# Controller.net
KiCad netlist of a schematic drawn in EAGLE
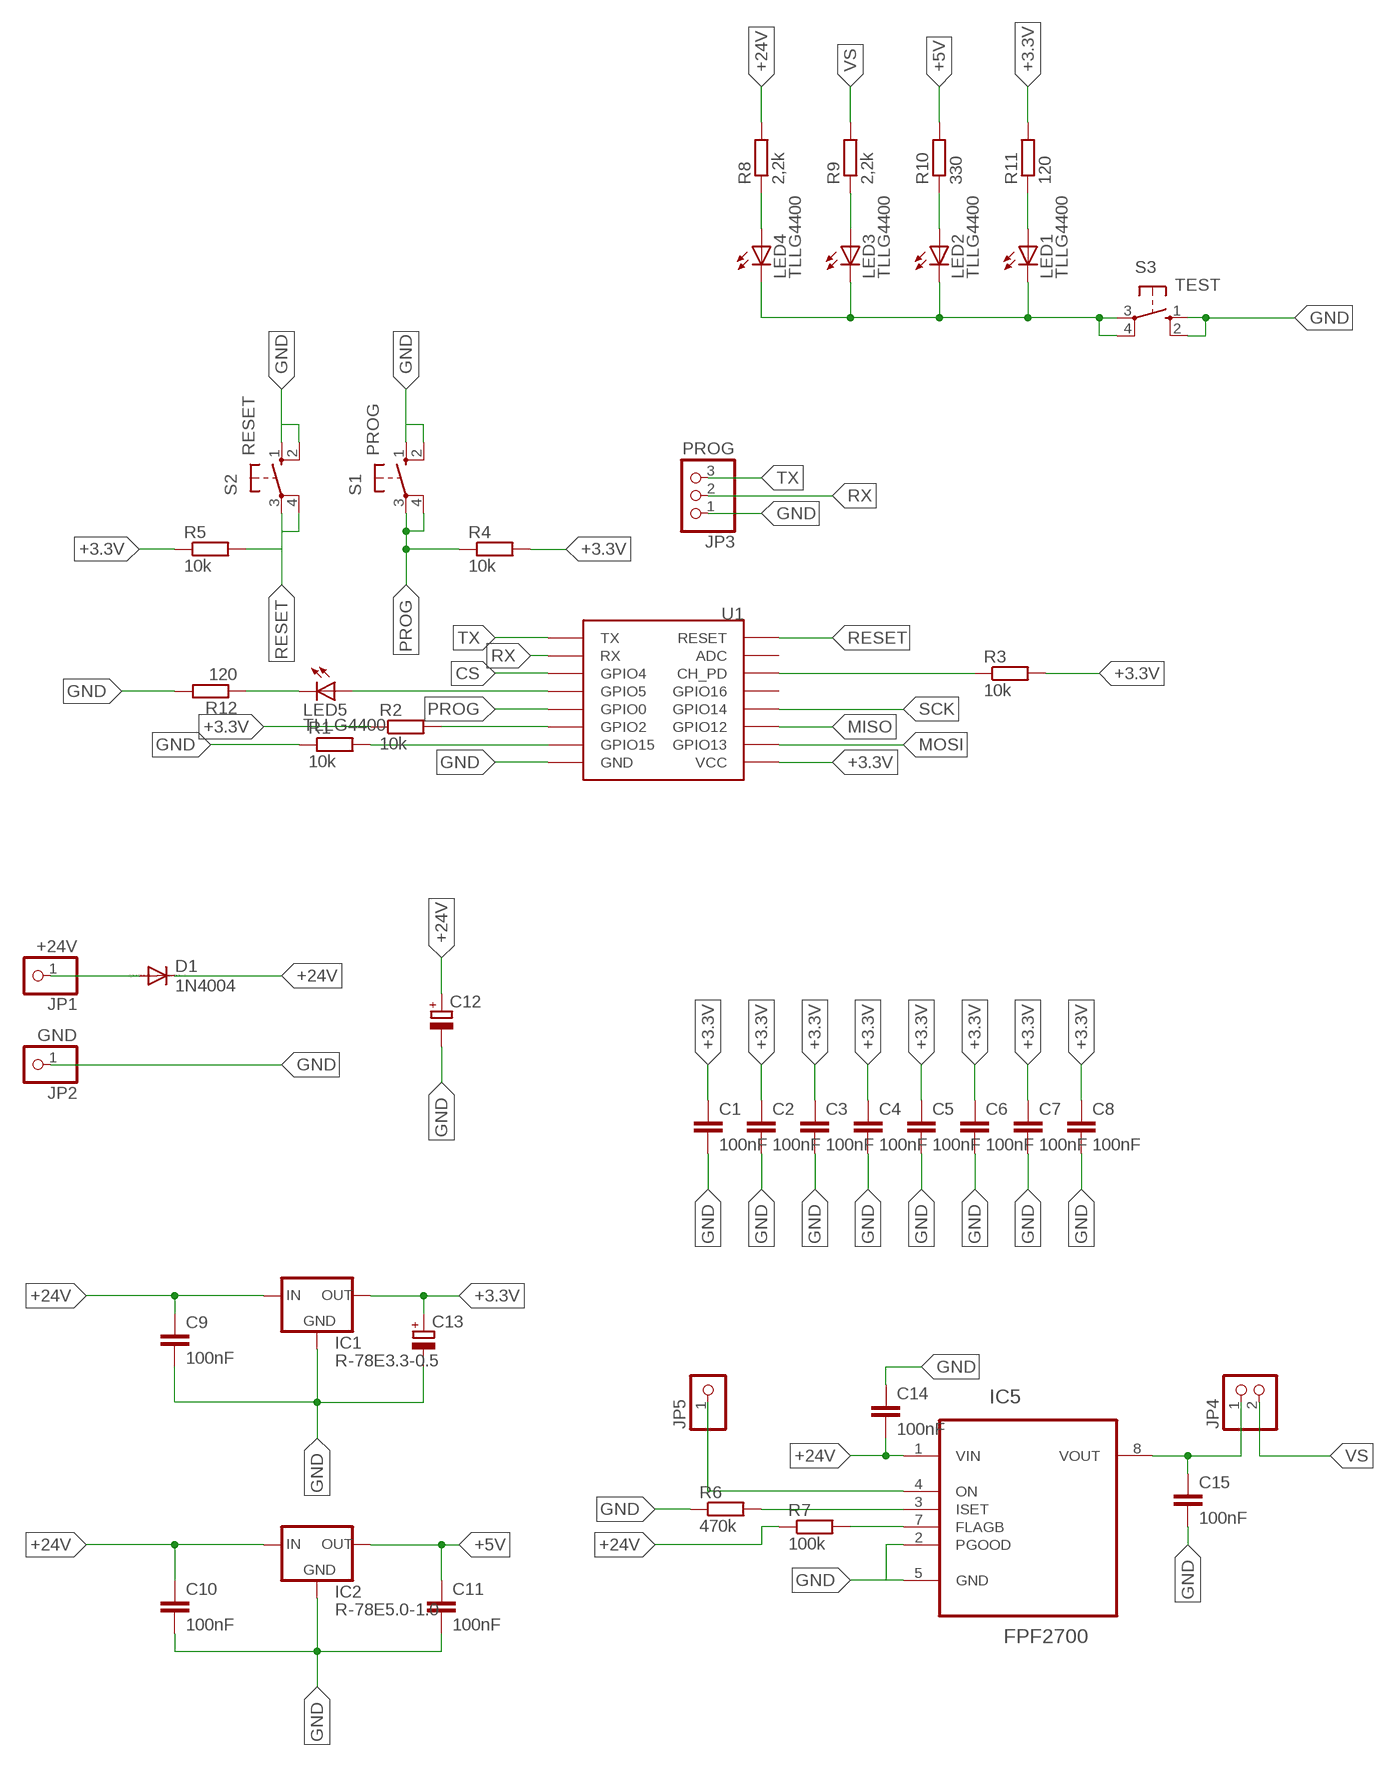
[diagram p0: schematic, sheet 1, part 1 of 2]
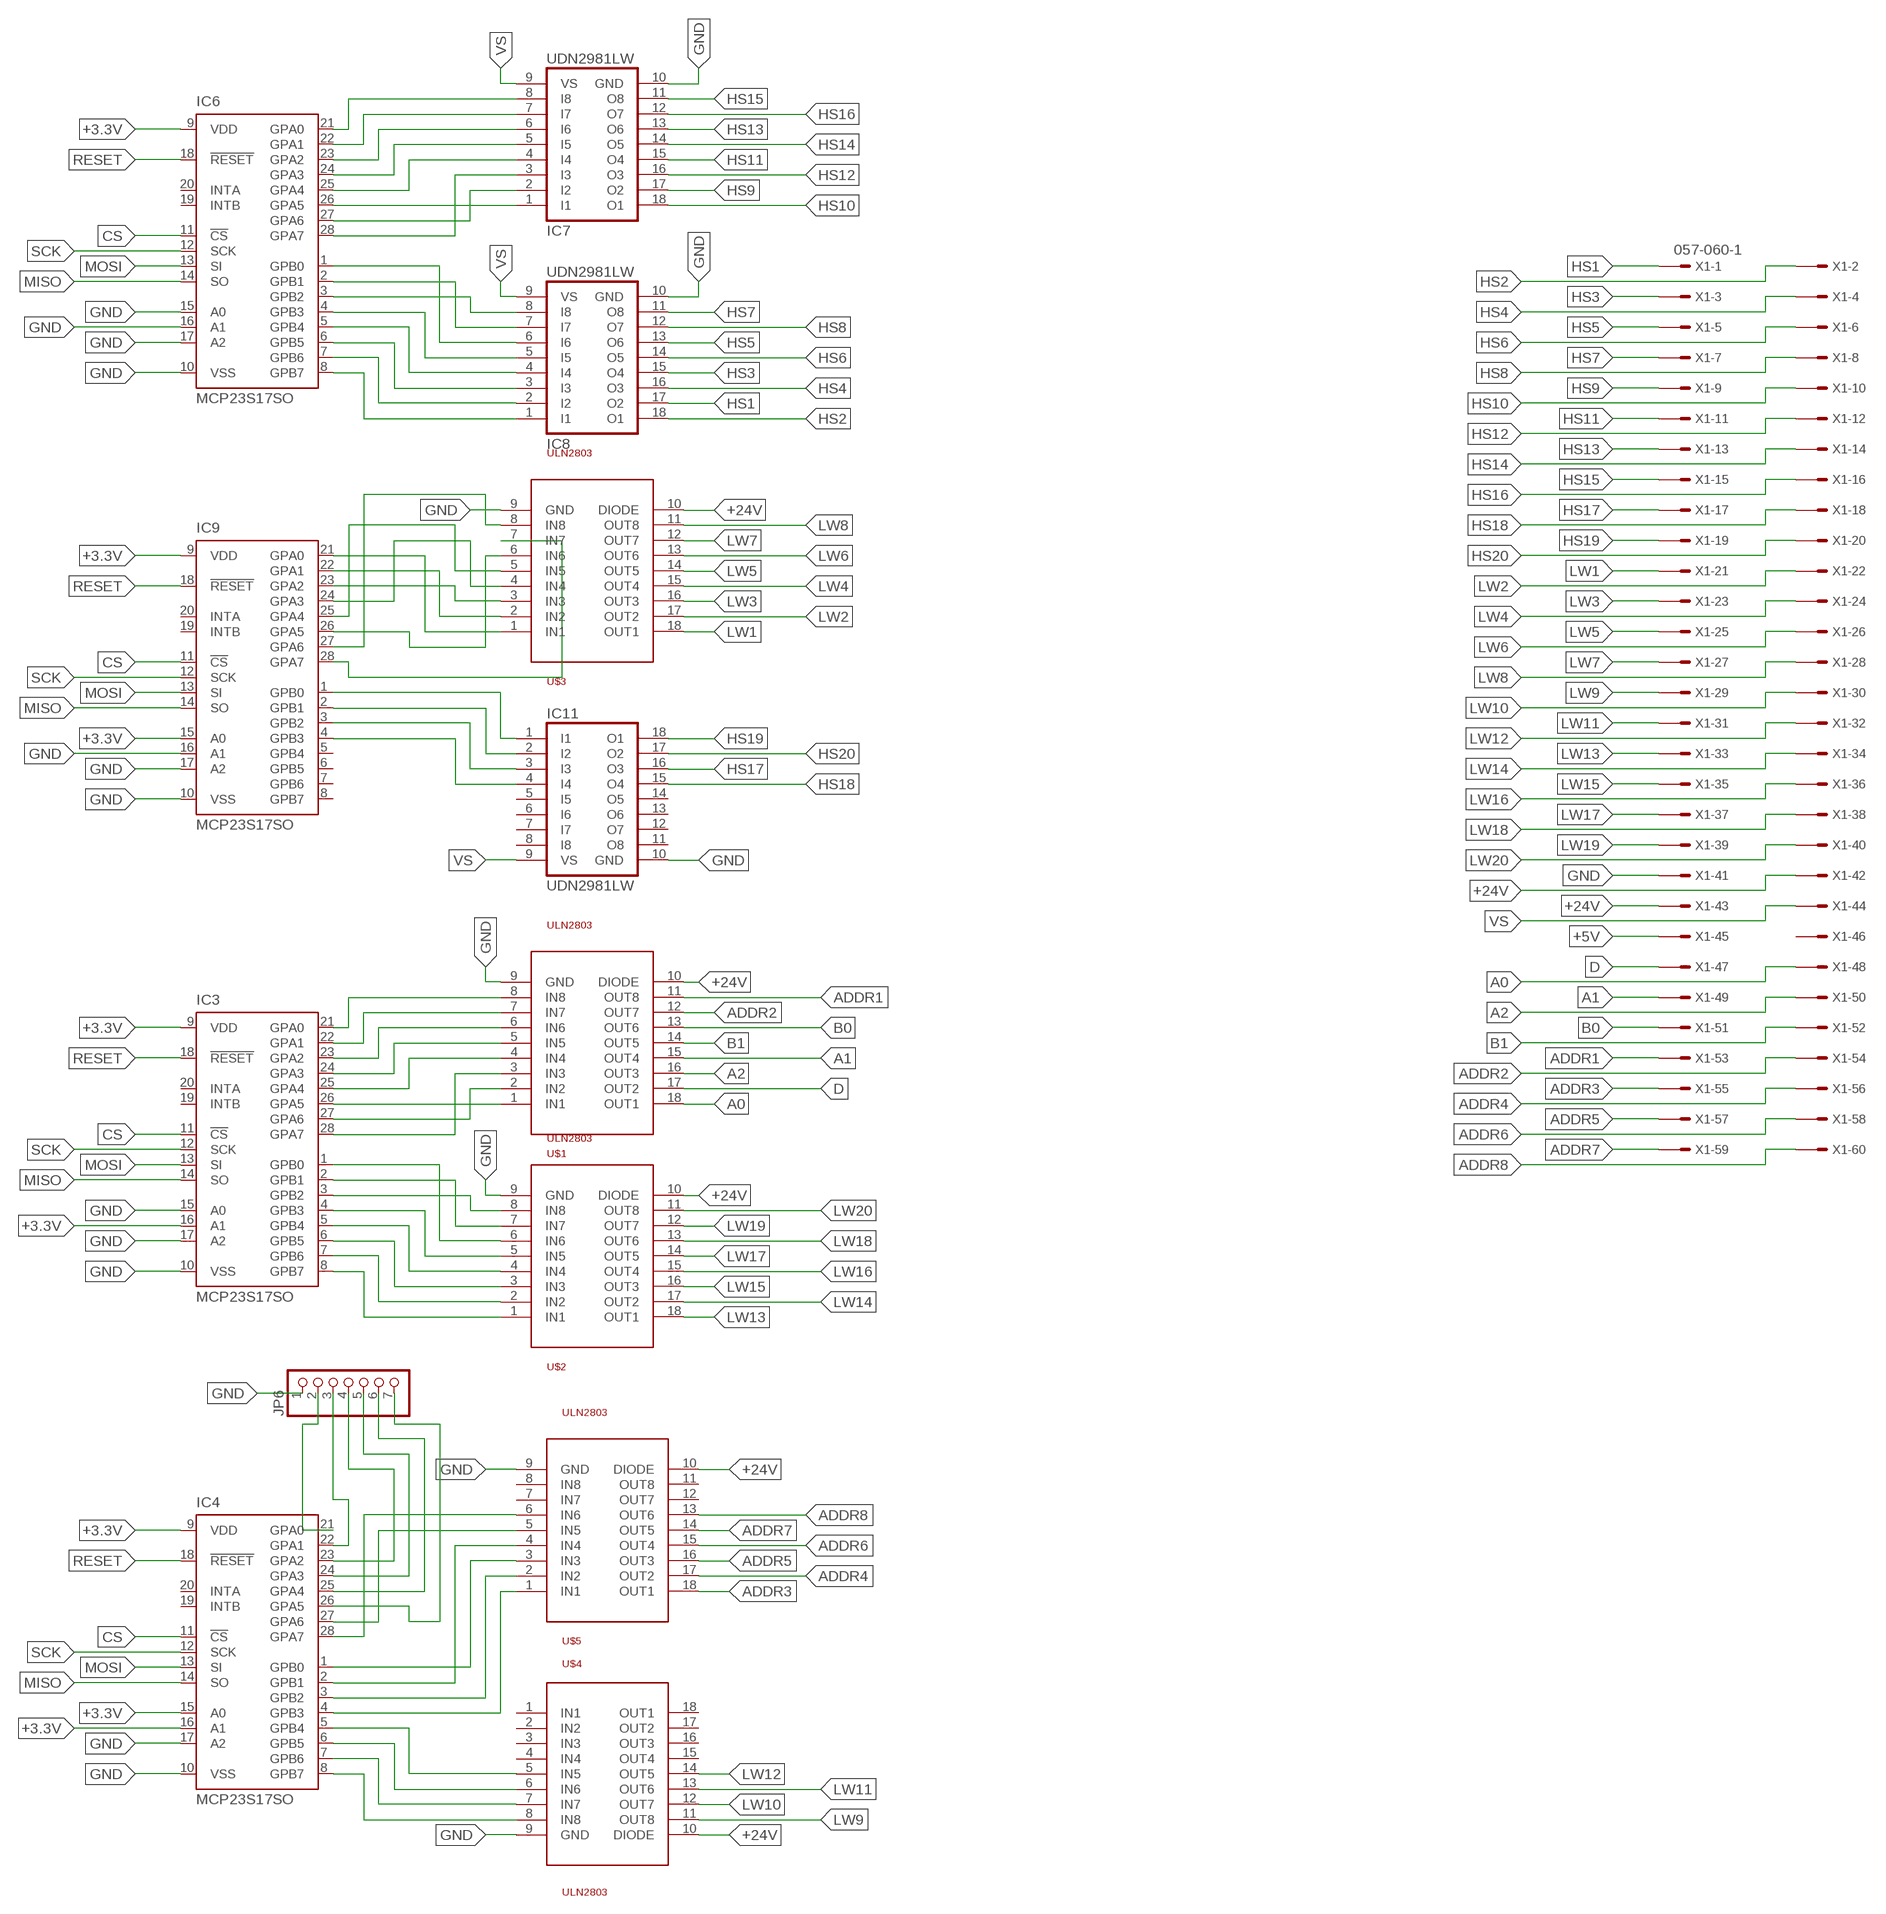
[diagram p1: schematic, sheet 1, part 2 of 2]

(export (version "E")
  (design (tool "Eeschema 10.0.6"))
  (components
    (comp (ref "C1")
      (value "100nF")
      (footprint "eagle-import:C1206")
      (libsource (lib "eagle-import") (part "C-EUC1206"))
    )
    (comp (ref "C2")
      (value "100nF")
      (footprint "eagle-import:C1206")
      (libsource (lib "eagle-import") (part "C-EUC1206"))
    )
    (comp (ref "C3")
      (value "100nF")
      (footprint "eagle-import:C1206")
      (libsource (lib "eagle-import") (part "C-EUC1206"))
    )
    (comp (ref "C4")
      (value "100nF")
      (footprint "eagle-import:C1206")
      (libsource (lib "eagle-import") (part "C-EUC1206"))
    )
    (comp (ref "C5")
      (value "100nF")
      (footprint "eagle-import:C1206")
      (libsource (lib "eagle-import") (part "C-EUC1206"))
    )
    (comp (ref "C6")
      (value "100nF")
      (footprint "eagle-import:C1206")
      (libsource (lib "eagle-import") (part "C-EUC1206"))
    )
    (comp (ref "C7")
      (value "100nF")
      (footprint "eagle-import:C1206")
      (libsource (lib "eagle-import") (part "C-EUC1206"))
    )
    (comp (ref "C8")
      (value "100nF")
      (footprint "eagle-import:C1206")
      (libsource (lib "eagle-import") (part "C-EUC1206"))
    )
    (comp (ref "C9")
      (value "100nF")
      (footprint "eagle-import:C1206")
      (libsource (lib "eagle-import") (part "C-EUC1206"))
    )
    (comp (ref "C10")
      (value "100nF")
      (footprint "eagle-import:C1206")
      (libsource (lib "eagle-import") (part "C-EUC1206"))
    )
    (comp (ref "C11")
      (value "100nF")
      (footprint "eagle-import:C1206")
      (libsource (lib "eagle-import") (part "C-EUC1206"))
    )
    (comp (ref "C12")
      (value "CPOL-EUE2.5-5")
      (footprint "eagle-import:E2,5-5")
      (libsource (lib "eagle-import") (part "CPOL-EUE2.5-5"))
    )
    (comp (ref "C13")
      (value "CPOL-EUE2.5-5")
      (footprint "eagle-import:E2,5-5")
      (libsource (lib "eagle-import") (part "CPOL-EUE2.5-5"))
    )
    (comp (ref "C14")
      (value "100nF")
      (footprint "eagle-import:C1206")
      (libsource (lib "eagle-import") (part "C-EUC1206"))
    )
    (comp (ref "C15")
      (value "100nF")
      (footprint "eagle-import:C1206")
      (libsource (lib "eagle-import") (part "C-EUC1206"))
    )
    (comp (ref "D1")
      (value "1N4004")
      (footprint "eagle-import:DO41-10")
      (libsource (lib "eagle-import") (part "1N4004"))
    )
    (comp (ref "IC1")
      (value "R-78E3.3-0.5")
      (footprint "eagle-import:SIP3")
      (fields (field (name "MF") "Recom") (field (name "MPN") "R-783.3-0.5"))
      (libsource (lib "eagle-import") (part "R-78E-0.53.3"))
    )
    (comp (ref "IC2")
      (value "R-78E5.0-1.0")
      (footprint "eagle-import:SIP3")
      (fields (field (name "MF") "Recom") (field (name "MPN") "R-785.0-1.0"))
      (libsource (lib "eagle-import") (part "R-78E-1.05.0"))
    )
    (comp (ref "IC3")
      (value "MCP23S17SO")
      (footprint "eagle-import:SO28W")
      (libsource (lib "eagle-import") (part "MCP23S17SO"))
    )
    (comp (ref "IC4")
      (value "MCP23S17SO")
      (footprint "eagle-import:SO28W")
      (libsource (lib "eagle-import") (part "MCP23S17SO"))
    )
    (comp (ref "IC5")
      (value "FPF2700")
      (footprint "eagle-import:SOIC127P600X175-8N")
      (libsource (lib "eagle-import") (part "FPF2700"))
    )
    (comp (ref "IC6")
      (value "MCP23S17SO")
      (footprint "eagle-import:SO28W")
      (libsource (lib "eagle-import") (part "MCP23S17SO"))
    )
    (comp (ref "IC7")
      (value "UDN2981LW")
      (footprint "eagle-import:SO18W")
      (libsource (lib "eagle-import") (part "UDN298LW1"))
    )
    (comp (ref "IC8")
      (value "UDN2981LW")
      (footprint "eagle-import:SO18W")
      (libsource (lib "eagle-import") (part "UDN298LW1"))
    )
    (comp (ref "IC9")
      (value "MCP23S17SO")
      (footprint "eagle-import:SO28W")
      (libsource (lib "eagle-import") (part "MCP23S17SO"))
    )
    (comp (ref "IC11")
      (value "UDN2981LW")
      (footprint "eagle-import:SO18W")
      (libsource (lib "eagle-import") (part "UDN298LW1"))
    )
    (comp (ref "JP1")
      (value "+24V")
      (footprint "eagle-import:1X01")
      (libsource (lib "eagle-import") (part "PINHD-1X1"))
    )
    (comp (ref "JP2")
      (value "GND")
      (footprint "eagle-import:1X01")
      (libsource (lib "eagle-import") (part "PINHD-1X1"))
    )
    (comp (ref "JP3")
      (value "PROG")
      (footprint "eagle-import:1X03")
      (libsource (lib "eagle-import") (part "PINHD-1X3"))
    )
    (comp (ref "JP4")
      (value "PINHD-1X2")
      (footprint "eagle-import:1X02")
      (libsource (lib "eagle-import") (part "PINHD-1X2"))
    )
    (comp (ref "JP5")
      (value "PINHD-1X1")
      (footprint "eagle-import:1X01")
      (libsource (lib "eagle-import") (part "PINHD-1X1"))
    )
    (comp (ref "JP6")
      (value "PINHD-1X7")
      (footprint "eagle-import:1X07")
      (libsource (lib "eagle-import") (part "PINHD-1X7"))
    )
    (comp (ref "LED1")
      (value "TLLG4400")
      (footprint "eagle-import:LED3MM")
      (fields (field (name "MF") "VISHAY SEMICONDUCTOR"))
      (libsource (lib "eagle-import") (part "TLLG4400"))
    )
    (comp (ref "LED2")
      (value "TLLG4400")
      (footprint "eagle-import:LED3MM")
      (fields (field (name "MF") "VISHAY SEMICONDUCTOR"))
      (libsource (lib "eagle-import") (part "TLLG4400"))
    )
    (comp (ref "LED3")
      (value "TLLG4400")
      (footprint "eagle-import:LED3MM")
      (fields (field (name "MF") "VISHAY SEMICONDUCTOR"))
      (libsource (lib "eagle-import") (part "TLLG4400"))
    )
    (comp (ref "LED4")
      (value "TLLG4400")
      (footprint "eagle-import:LED3MM")
      (fields (field (name "MF") "VISHAY SEMICONDUCTOR"))
      (libsource (lib "eagle-import") (part "TLLG4400"))
    )
    (comp (ref "LED5")
      (value "TLLG4400")
      (footprint "eagle-import:LED3MM")
      (fields (field (name "MF") "VISHAY SEMICONDUCTOR"))
      (libsource (lib "eagle-import") (part "TLLG4400"))
    )
    (comp (ref "R1")
      (value "10k")
      (footprint "eagle-import:R1206")
      (libsource (lib "eagle-import") (part "R-EU_R1206"))
    )
    (comp (ref "R2")
      (value "10k")
      (footprint "eagle-import:R1206")
      (libsource (lib "eagle-import") (part "R-EU_R1206"))
    )
    (comp (ref "R3")
      (value "10k")
      (footprint "eagle-import:R1206")
      (libsource (lib "eagle-import") (part "R-EU_R1206"))
    )
    (comp (ref "R4")
      (value "10k")
      (footprint "eagle-import:R1206")
      (libsource (lib "eagle-import") (part "R-EU_R1206"))
    )
    (comp (ref "R5")
      (value "10k")
      (footprint "eagle-import:R1206")
      (libsource (lib "eagle-import") (part "R-EU_R1206"))
    )
    (comp (ref "R6")
      (value "470k")
      (footprint "eagle-import:0207_10")
      (libsource (lib "eagle-import") (part "R-EU_0207/10"))
    )
    (comp (ref "R7")
      (value "100k")
      (footprint "eagle-import:0207_10")
      (libsource (lib "eagle-import") (part "R-EU_0207/10"))
    )
    (comp (ref "R8")
      (value "2,2k")
      (footprint "eagle-import:R1206")
      (libsource (lib "eagle-import") (part "R-EU_R1206"))
    )
    (comp (ref "R9")
      (value "2,2k")
      (footprint "eagle-import:R1206")
      (libsource (lib "eagle-import") (part "R-EU_R1206"))
    )
    (comp (ref "R10")
      (value "330")
      (footprint "eagle-import:R1206")
      (libsource (lib "eagle-import") (part "R-EU_R1206"))
    )
    (comp (ref "R11")
      (value "120")
      (footprint "eagle-import:R1206")
      (libsource (lib "eagle-import") (part "R-EU_R1206"))
    )
    (comp (ref "R12")
      (value "120")
      (footprint "eagle-import:R1206")
      (libsource (lib "eagle-import") (part "R-EU_R1206"))
    )
    (comp (ref "S1")
      (value "PROG")
      (footprint "eagle-import:B3F-10XX")
      (fields (field (name "MPN") "B3F-1000"))
      (libsource (lib "eagle-import") (part "10-XX"))
    )
    (comp (ref "S2")
      (value "RESET")
      (footprint "eagle-import:B3F-10XX")
      (fields (field (name "MPN") "B3F-1000"))
      (libsource (lib "eagle-import") (part "10-XX"))
    )
    (comp (ref "S3")
      (value "TEST")
      (footprint "eagle-import:B3F-10XX")
      (fields (field (name "MPN") "B3F-1000"))
      (libsource (lib "eagle-import") (part "10-XX"))
    )
    (comp (ref "U$1")
      (value "ULN2803")
      (footprint "eagle-import:SO18L")
      (libsource (lib "eagle-import") (part "ULN2803"))
    )
    (comp (ref "U$2")
      (value "ULN2803")
      (footprint "eagle-import:SO18L")
      (libsource (lib "eagle-import") (part "ULN2803"))
    )
    (comp (ref "U$3")
      (value "ULN2803")
      (footprint "eagle-import:SO18L")
      (libsource (lib "eagle-import") (part "ULN2803"))
    )
    (comp (ref "U$4")
      (value "ULN2803")
      (footprint "eagle-import:SO18L")
      (libsource (lib "eagle-import") (part "ULN2803"))
    )
    (comp (ref "U$5")
      (value "ULN2803")
      (footprint "eagle-import:SO18L")
      (libsource (lib "eagle-import") (part "ULN2803"))
    )
    (comp (ref "U1")
      (value "ESP12SMD")
      (footprint "eagle-import:ESP12-SMD")
      (libsource (lib "eagle-import") (part "ESP12SMD"))
    )
    (comp (ref "X1")
      (value "057-060-1")
      (footprint "eagle-import:057-060-1")
      (libsource (lib "eagle-import") (part "057-060-1"))
    )
  )
  (nets
    (net (code "1") (name "+3.3V") (class "Default")
      (node (ref "C1") (pin "1") (pinfunction "1_1") (pintype "passive"))
      (node (ref "C13") (pin "+") (pinfunction "+_+") (pintype "passive"))
      (node (ref "C2") (pin "1") (pinfunction "1_1") (pintype "passive"))
      (node (ref "C3") (pin "1") (pinfunction "1_1") (pintype "passive"))
      (node (ref "C4") (pin "1") (pinfunction "1_1") (pintype "passive"))
      (node (ref "C5") (pin "1") (pinfunction "1_1") (pintype "passive"))
      (node (ref "C6") (pin "1") (pinfunction "1_1") (pintype "passive"))
      (node (ref "C7") (pin "1") (pinfunction "1_1") (pintype "passive"))
      (node (ref "C8") (pin "1") (pinfunction "1_1") (pintype "passive"))
      (node (ref "IC1") (pin "3") (pinfunction "OUT_3") (pintype "passive"))
      (node (ref "IC3") (pin "16") (pinfunction "A1_16") (pintype "input"))
      (node (ref "IC3") (pin "9") (pinfunction "VDD_9") (pintype "power_in"))
      (node (ref "IC4") (pin "15") (pinfunction "A0_15") (pintype "input"))
      (node (ref "IC4") (pin "16") (pinfunction "A1_16") (pintype "input"))
      (node (ref "IC4") (pin "9") (pinfunction "VDD_9") (pintype "power_in"))
      (node (ref "IC6") (pin "9") (pinfunction "VDD_9") (pintype "power_in"))
      (node (ref "IC9") (pin "15") (pinfunction "A0_15") (pintype "input"))
      (node (ref "IC9") (pin "9") (pinfunction "VDD_9") (pintype "power_in"))
      (node (ref "R11") (pin "2") (pinfunction "2_2") (pintype "passive"))
      (node (ref "R2") (pin "1") (pinfunction "1_1") (pintype "passive"))
      (node (ref "R3") (pin "2") (pinfunction "2_2") (pintype "passive"))
      (node (ref "R4") (pin "2") (pinfunction "2_2") (pintype "passive"))
      (node (ref "R5") (pin "1") (pinfunction "1_1") (pintype "passive"))
      (node (ref "U1") (pin "VCC") (pinfunction "VCC_VCC") (pintype "bidirectional"))
    )
    (net (code "2") (name "+5V") (class "Default")
      (node (ref "C11") (pin "1") (pinfunction "1_1") (pintype "passive"))
      (node (ref "IC2") (pin "3") (pinfunction "OUT_3") (pintype "passive"))
      (node (ref "R10") (pin "2") (pinfunction "2_2") (pintype "passive"))
      (node (ref "X1") (pin "45") (pinfunction "S_45") (pintype "passive"))
    )
    (net (code "3") (name "+24V") (class "Default")
      (node (ref "C10") (pin "1") (pinfunction "1_1") (pintype "passive"))
      (node (ref "C12") (pin "+") (pinfunction "+_+") (pintype "passive"))
      (node (ref "C14") (pin "2") (pinfunction "2_2") (pintype "passive"))
      (node (ref "C9") (pin "1") (pinfunction "1_1") (pintype "passive"))
      (node (ref "D1") (pin "C") (pinfunction "C_C") (pintype "passive"))
      (node (ref "IC1") (pin "1") (pinfunction "IN_1") (pintype "input"))
      (node (ref "IC2") (pin "1") (pinfunction "IN_1") (pintype "input"))
      (node (ref "IC5") (pin "1") (pinfunction "VIN_1") (pintype "power_in"))
      (node (ref "R7") (pin "1") (pinfunction "1_1") (pintype "passive"))
      (node (ref "R8") (pin "2") (pinfunction "2_2") (pintype "passive"))
      (node (ref "U$1") (pin "10") (pinfunction "DIODE_10") (pintype "power_in"))
      (node (ref "U$2") (pin "10") (pinfunction "DIODE_10") (pintype "power_in"))
      (node (ref "U$3") (pin "10") (pinfunction "DIODE_10") (pintype "power_in"))
      (node (ref "U$4") (pin "10") (pinfunction "DIODE_10") (pintype "power_in"))
      (node (ref "U$5") (pin "10") (pinfunction "DIODE_10") (pintype "power_in"))
      (node (ref "X1") (pin "42") (pinfunction "S_42") (pintype "passive"))
      (node (ref "X1") (pin "43") (pinfunction "S_43") (pintype "passive"))
    )
    (net (code "4") (name "A0") (class "Default")
      (node (ref "U$1") (pin "18") (pinfunction "OUT1_18") (pintype "open_collector"))
      (node (ref "X1") (pin "48") (pinfunction "S_48") (pintype "passive"))
    )
    (net (code "5") (name "A1") (class "Default")
      (node (ref "U$1") (pin "15") (pinfunction "OUT4_15") (pintype "open_collector"))
      (node (ref "X1") (pin "49") (pinfunction "S_49") (pintype "passive"))
    )
    (net (code "6") (name "A2") (class "Default")
      (node (ref "U$1") (pin "16") (pinfunction "OUT3_16") (pintype "open_collector"))
      (node (ref "X1") (pin "50") (pinfunction "S_50") (pintype "passive"))
    )
    (net (code "7") (name "ADDR1") (class "Default")
      (node (ref "U$1") (pin "11") (pinfunction "OUT8_11") (pintype "open_collector"))
      (node (ref "X1") (pin "53") (pinfunction "S_53") (pintype "passive"))
    )
    (net (code "8") (name "ADDR2") (class "Default")
      (node (ref "U$1") (pin "12") (pinfunction "OUT7_12") (pintype "open_collector"))
      (node (ref "X1") (pin "54") (pinfunction "S_54") (pintype "passive"))
    )
    (net (code "9") (name "ADDR3") (class "Default")
      (node (ref "U$5") (pin "18") (pinfunction "OUT1_18") (pintype "open_collector"))
      (node (ref "X1") (pin "55") (pinfunction "S_55") (pintype "passive"))
    )
    (net (code "10") (name "ADDR4") (class "Default")
      (node (ref "U$5") (pin "17") (pinfunction "OUT2_17") (pintype "open_collector"))
      (node (ref "X1") (pin "56") (pinfunction "S_56") (pintype "passive"))
    )
    (net (code "11") (name "ADDR5") (class "Default")
      (node (ref "U$5") (pin "16") (pinfunction "OUT3_16") (pintype "open_collector"))
      (node (ref "X1") (pin "57") (pinfunction "S_57") (pintype "passive"))
    )
    (net (code "12") (name "ADDR6") (class "Default")
      (node (ref "U$5") (pin "15") (pinfunction "OUT4_15") (pintype "open_collector"))
      (node (ref "X1") (pin "58") (pinfunction "S_58") (pintype "passive"))
    )
    (net (code "13") (name "ADDR7") (class "Default")
      (node (ref "U$5") (pin "14") (pinfunction "OUT5_14") (pintype "open_collector"))
      (node (ref "X1") (pin "59") (pinfunction "S_59") (pintype "passive"))
    )
    (net (code "14") (name "ADDR8") (class "Default")
      (node (ref "U$5") (pin "13") (pinfunction "OUT6_13") (pintype "open_collector"))
      (node (ref "X1") (pin "60") (pinfunction "S_60") (pintype "passive"))
    )
    (net (code "15") (name "B0") (class "Default")
      (node (ref "U$1") (pin "13") (pinfunction "OUT6_13") (pintype "open_collector"))
      (node (ref "X1") (pin "51") (pinfunction "S_51") (pintype "passive"))
    )
    (net (code "16") (name "B1") (class "Default")
      (node (ref "U$1") (pin "14") (pinfunction "OUT5_14") (pintype "open_collector"))
      (node (ref "X1") (pin "52") (pinfunction "S_52") (pintype "passive"))
    )
    (net (code "17") (name "CS") (class "Default")
      (node (ref "IC3") (pin "11") (pinfunction "~{CS}_11") (pintype "input"))
      (node (ref "IC4") (pin "11") (pinfunction "~{CS}_11") (pintype "input"))
      (node (ref "IC6") (pin "11") (pinfunction "~{CS}_11") (pintype "input"))
      (node (ref "IC9") (pin "11") (pinfunction "~{CS}_11") (pintype "input"))
      (node (ref "U1") (pin "GPIO4") (pinfunction "GPIO4_GPIO4") (pintype "bidirectional"))
    )
    (net (code "18") (name "D") (class "Default")
      (node (ref "U$1") (pin "17") (pinfunction "OUT2_17") (pintype "open_collector"))
      (node (ref "X1") (pin "47") (pinfunction "S_47") (pintype "passive"))
    )
    (net (code "19") (name "GND") (class "Default")
      (node (ref "C1") (pin "2") (pinfunction "2_2") (pintype "passive"))
      (node (ref "C10") (pin "2") (pinfunction "2_2") (pintype "passive"))
      (node (ref "C11") (pin "2") (pinfunction "2_2") (pintype "passive"))
      (node (ref "C12") (pin "-") (pinfunction "-_-") (pintype "passive"))
      (node (ref "C13") (pin "-") (pinfunction "-_-") (pintype "passive"))
      (node (ref "C14") (pin "1") (pinfunction "1_1") (pintype "passive"))
      (node (ref "C15") (pin "2") (pinfunction "2_2") (pintype "passive"))
      (node (ref "C2") (pin "2") (pinfunction "2_2") (pintype "passive"))
      (node (ref "C3") (pin "2") (pinfunction "2_2") (pintype "passive"))
      (node (ref "C4") (pin "2") (pinfunction "2_2") (pintype "passive"))
      (node (ref "C5") (pin "2") (pinfunction "2_2") (pintype "passive"))
      (node (ref "C6") (pin "2") (pinfunction "2_2") (pintype "passive"))
      (node (ref "C7") (pin "2") (pinfunction "2_2") (pintype "passive"))
      (node (ref "C8") (pin "2") (pinfunction "2_2") (pintype "passive"))
      (node (ref "C9") (pin "2") (pinfunction "2_2") (pintype "passive"))
      (node (ref "IC1") (pin "2") (pinfunction "GND_2") (pintype "input"))
      (node (ref "IC11") (pin "10") (pinfunction "GND_10") (pintype "power_in"))
      (node (ref "IC2") (pin "2") (pinfunction "GND_2") (pintype "input"))
      (node (ref "IC3") (pin "10") (pinfunction "VSS_10") (pintype "power_in"))
      (node (ref "IC3") (pin "15") (pinfunction "A0_15") (pintype "input"))
      (node (ref "IC3") (pin "17") (pinfunction "A2_17") (pintype "input"))
      (node (ref "IC4") (pin "10") (pinfunction "VSS_10") (pintype "power_in"))
      (node (ref "IC4") (pin "17") (pinfunction "A2_17") (pintype "input"))
      (node (ref "IC5") (pin "2") (pinfunction "PGOOD_2") (pintype "output"))
      (node (ref "IC5") (pin "5") (pinfunction "GND_5") (pintype "passive"))
      (node (ref "IC6") (pin "10") (pinfunction "VSS_10") (pintype "power_in"))
      (node (ref "IC6") (pin "15") (pinfunction "A0_15") (pintype "input"))
      (node (ref "IC6") (pin "16") (pinfunction "A1_16") (pintype "input"))
      (node (ref "IC6") (pin "17") (pinfunction "A2_17") (pintype "input"))
      (node (ref "IC7") (pin "10") (pinfunction "GND_10") (pintype "power_in"))
      (node (ref "IC8") (pin "10") (pinfunction "GND_10") (pintype "power_in"))
      (node (ref "IC9") (pin "10") (pinfunction "VSS_10") (pintype "power_in"))
      (node (ref "IC9") (pin "16") (pinfunction "A1_16") (pintype "input"))
      (node (ref "IC9") (pin "17") (pinfunction "A2_17") (pintype "input"))
      (node (ref "JP2") (pin "1") (pinfunction "1_1") (pintype "passive"))
      (node (ref "JP3") (pin "1") (pinfunction "1_1") (pintype "passive"))
      (node (ref "JP6") (pin "1") (pinfunction "1_1") (pintype "passive"))
      (node (ref "R1") (pin "1") (pinfunction "1_1") (pintype "passive"))
      (node (ref "R12") (pin "2") (pinfunction "2_2") (pintype "passive"))
      (node (ref "R6") (pin "1") (pinfunction "1_1") (pintype "passive"))
      (node (ref "S1") (pin "1") (pinfunction "S_1") (pintype "passive"))
      (node (ref "S1") (pin "2") (pinfunction "S1_2") (pintype "passive"))
      (node (ref "S2") (pin "1") (pinfunction "S_1") (pintype "passive"))
      (node (ref "S2") (pin "2") (pinfunction "S1_2") (pintype "passive"))
      (node (ref "S3") (pin "1") (pinfunction "S_1") (pintype "passive"))
      (node (ref "S3") (pin "2") (pinfunction "S1_2") (pintype "passive"))
      (node (ref "U$1") (pin "9") (pinfunction "GND_9") (pintype "power_in"))
      (node (ref "U$2") (pin "9") (pinfunction "GND_9") (pintype "power_in"))
      (node (ref "U$3") (pin "9") (pinfunction "GND_9") (pintype "power_in"))
      (node (ref "U$4") (pin "9") (pinfunction "GND_9") (pintype "power_in"))
      (node (ref "U$5") (pin "9") (pinfunction "GND_9") (pintype "power_in"))
      (node (ref "U1") (pin "GND") (pinfunction "GND_GND") (pintype "bidirectional"))
      (node (ref "X1") (pin "41") (pinfunction "S_41") (pintype "passive"))
    )
    (net (code "20") (name "HS1") (class "Default")
      (node (ref "IC8") (pin "17") (pinfunction "O2_17") (pintype "open_collector"))
      (node (ref "X1") (pin "1") (pinfunction "S_1") (pintype "passive"))
    )
    (net (code "21") (name "HS2") (class "Default")
      (node (ref "IC8") (pin "18") (pinfunction "O1_18") (pintype "open_collector"))
      (node (ref "X1") (pin "2") (pinfunction "S_2") (pintype "passive"))
    )
    (net (code "22") (name "HS3") (class "Default")
      (node (ref "IC8") (pin "15") (pinfunction "O4_15") (pintype "open_collector"))
      (node (ref "X1") (pin "3") (pinfunction "S_3") (pintype "passive"))
    )
    (net (code "23") (name "HS4") (class "Default")
      (node (ref "IC8") (pin "16") (pinfunction "O3_16") (pintype "open_collector"))
      (node (ref "X1") (pin "4") (pinfunction "S_4") (pintype "passive"))
    )
    (net (code "24") (name "HS5") (class "Default")
      (node (ref "IC8") (pin "13") (pinfunction "O6_13") (pintype "open_collector"))
      (node (ref "X1") (pin "5") (pinfunction "S_5") (pintype "passive"))
    )
    (net (code "25") (name "HS6") (class "Default")
      (node (ref "IC8") (pin "14") (pinfunction "O5_14") (pintype "open_collector"))
      (node (ref "X1") (pin "6") (pinfunction "S_6") (pintype "passive"))
    )
    (net (code "26") (name "HS7") (class "Default")
      (node (ref "IC8") (pin "11") (pinfunction "O8_11") (pintype "open_collector"))
      (node (ref "X1") (pin "7") (pinfunction "S_7") (pintype "passive"))
    )
    (net (code "27") (name "HS8") (class "Default")
      (node (ref "IC8") (pin "12") (pinfunction "O7_12") (pintype "open_collector"))
      (node (ref "X1") (pin "8") (pinfunction "S_8") (pintype "passive"))
    )
    (net (code "28") (name "HS9") (class "Default")
      (node (ref "IC7") (pin "17") (pinfunction "O2_17") (pintype "open_collector"))
      (node (ref "X1") (pin "9") (pinfunction "S_9") (pintype "passive"))
    )
    (net (code "29") (name "HS10") (class "Default")
      (node (ref "IC7") (pin "18") (pinfunction "O1_18") (pintype "open_collector"))
      (node (ref "X1") (pin "10") (pinfunction "S_10") (pintype "passive"))
    )
    (net (code "30") (name "HS11") (class "Default")
      (node (ref "IC7") (pin "15") (pinfunction "O4_15") (pintype "open_collector"))
      (node (ref "X1") (pin "11") (pinfunction "S_11") (pintype "passive"))
    )
    (net (code "31") (name "HS12") (class "Default")
      (node (ref "IC7") (pin "16") (pinfunction "O3_16") (pintype "open_collector"))
      (node (ref "X1") (pin "12") (pinfunction "S_12") (pintype "passive"))
    )
    (net (code "32") (name "HS13") (class "Default")
      (node (ref "IC7") (pin "13") (pinfunction "O6_13") (pintype "open_collector"))
      (node (ref "X1") (pin "13") (pinfunction "S_13") (pintype "passive"))
    )
    (net (code "33") (name "HS14") (class "Default")
      (node (ref "IC7") (pin "14") (pinfunction "O5_14") (pintype "open_collector"))
      (node (ref "X1") (pin "14") (pinfunction "S_14") (pintype "passive"))
    )
    (net (code "34") (name "HS15") (class "Default")
      (node (ref "IC7") (pin "11") (pinfunction "O8_11") (pintype "open_collector"))
      (node (ref "X1") (pin "15") (pinfunction "S_15") (pintype "passive"))
    )
    (net (code "35") (name "HS16") (class "Default")
      (node (ref "IC7") (pin "12") (pinfunction "O7_12") (pintype "open_collector"))
      (node (ref "X1") (pin "16") (pinfunction "S_16") (pintype "passive"))
    )
    (net (code "36") (name "HS17") (class "Default")
      (node (ref "IC11") (pin "16") (pinfunction "O3_16") (pintype "open_collector"))
      (node (ref "X1") (pin "17") (pinfunction "S_17") (pintype "passive"))
    )
    (net (code "37") (name "HS18") (class "Default")
      (node (ref "IC11") (pin "15") (pinfunction "O4_15") (pintype "open_collector"))
      (node (ref "X1") (pin "18") (pinfunction "S_18") (pintype "passive"))
    )
    (net (code "38") (name "HS19") (class "Default")
      (node (ref "IC11") (pin "18") (pinfunction "O1_18") (pintype "open_collector"))
      (node (ref "X1") (pin "19") (pinfunction "S_19") (pintype "passive"))
    )
    (net (code "39") (name "HS20") (class "Default")
      (node (ref "IC11") (pin "17") (pinfunction "O2_17") (pintype "open_collector"))
      (node (ref "X1") (pin "20") (pinfunction "S_20") (pintype "passive"))
    )
    (net (code "40") (name "LW1") (class "Default")
      (node (ref "U$3") (pin "18") (pinfunction "OUT1_18") (pintype "open_collector"))
      (node (ref "X1") (pin "21") (pinfunction "S_21") (pintype "passive"))
    )
    (net (code "41") (name "LW2") (class "Default")
      (node (ref "U$3") (pin "17") (pinfunction "OUT2_17") (pintype "open_collector"))
      (node (ref "X1") (pin "22") (pinfunction "S_22") (pintype "passive"))
    )
    (net (code "42") (name "LW3") (class "Default")
      (node (ref "U$3") (pin "16") (pinfunction "OUT3_16") (pintype "open_collector"))
      (node (ref "X1") (pin "23") (pinfunction "S_23") (pintype "passive"))
    )
    (net (code "43") (name "LW4") (class "Default")
      (node (ref "U$3") (pin "15") (pinfunction "OUT4_15") (pintype "open_collector"))
      (node (ref "X1") (pin "24") (pinfunction "S_24") (pintype "passive"))
    )
    (net (code "44") (name "LW5") (class "Default")
      (node (ref "U$3") (pin "14") (pinfunction "OUT5_14") (pintype "open_collector"))
      (node (ref "X1") (pin "25") (pinfunction "S_25") (pintype "passive"))
    )
    (net (code "45") (name "LW6") (class "Default")
      (node (ref "U$3") (pin "13") (pinfunction "OUT6_13") (pintype "open_collector"))
      (node (ref "X1") (pin "26") (pinfunction "S_26") (pintype "passive"))
    )
    (net (code "46") (name "LW7") (class "Default")
      (node (ref "U$3") (pin "12") (pinfunction "OUT7_12") (pintype "open_collector"))
      (node (ref "X1") (pin "27") (pinfunction "S_27") (pintype "passive"))
    )
    (net (code "47") (name "LW8") (class "Default")
      (node (ref "U$3") (pin "11") (pinfunction "OUT8_11") (pintype "open_collector"))
      (node (ref "X1") (pin "28") (pinfunction "S_28") (pintype "passive"))
    )
    (net (code "48") (name "LW9") (class "Default")
      (node (ref "U$4") (pin "11") (pinfunction "OUT8_11") (pintype "open_collector"))
      (node (ref "X1") (pin "29") (pinfunction "S_29") (pintype "passive"))
    )
    (net (code "49") (name "LW10") (class "Default")
      (node (ref "U$4") (pin "12") (pinfunction "OUT7_12") (pintype "open_collector"))
      (node (ref "X1") (pin "30") (pinfunction "S_30") (pintype "passive"))
    )
    (net (code "50") (name "LW11") (class "Default")
      (node (ref "U$4") (pin "13") (pinfunction "OUT6_13") (pintype "open_collector"))
      (node (ref "X1") (pin "31") (pinfunction "S_31") (pintype "passive"))
    )
    (net (code "51") (name "LW12") (class "Default")
      (node (ref "U$4") (pin "14") (pinfunction "OUT5_14") (pintype "open_collector"))
      (node (ref "X1") (pin "32") (pinfunction "S_32") (pintype "passive"))
    )
    (net (code "52") (name "LW13") (class "Default")
      (node (ref "U$2") (pin "18") (pinfunction "OUT1_18") (pintype "open_collector"))
      (node (ref "X1") (pin "33") (pinfunction "S_33") (pintype "passive"))
    )
    (net (code "53") (name "LW14") (class "Default")
      (node (ref "U$2") (pin "17") (pinfunction "OUT2_17") (pintype "open_collector"))
      (node (ref "X1") (pin "34") (pinfunction "S_34") (pintype "passive"))
    )
    (net (code "54") (name "LW15") (class "Default")
      (node (ref "U$2") (pin "16") (pinfunction "OUT3_16") (pintype "open_collector"))
      (node (ref "X1") (pin "35") (pinfunction "S_35") (pintype "passive"))
    )
    (net (code "55") (name "LW16") (class "Default")
      (node (ref "U$2") (pin "15") (pinfunction "OUT4_15") (pintype "open_collector"))
      (node (ref "X1") (pin "36") (pinfunction "S_36") (pintype "passive"))
    )
    (net (code "56") (name "LW17") (class "Default")
      (node (ref "U$2") (pin "14") (pinfunction "OUT5_14") (pintype "open_collector"))
      (node (ref "X1") (pin "37") (pinfunction "S_37") (pintype "passive"))
    )
    (net (code "57") (name "LW18") (class "Default")
      (node (ref "U$2") (pin "13") (pinfunction "OUT6_13") (pintype "open_collector"))
      (node (ref "X1") (pin "38") (pinfunction "S_38") (pintype "passive"))
    )
    (net (code "58") (name "LW19") (class "Default")
      (node (ref "U$2") (pin "12") (pinfunction "OUT7_12") (pintype "open_collector"))
      (node (ref "X1") (pin "39") (pinfunction "S_39") (pintype "passive"))
    )
    (net (code "59") (name "LW20") (class "Default")
      (node (ref "U$2") (pin "11") (pinfunction "OUT8_11") (pintype "open_collector"))
      (node (ref "X1") (pin "40") (pinfunction "S_40") (pintype "passive"))
    )
    (net (code "60") (name "MISO") (class "Default")
      (node (ref "IC3") (pin "14") (pinfunction "SO_14") (pintype "output"))
      (node (ref "IC4") (pin "14") (pinfunction "SO_14") (pintype "output"))
      (node (ref "IC6") (pin "14") (pinfunction "SO_14") (pintype "output"))
      (node (ref "IC9") (pin "14") (pinfunction "SO_14") (pintype "output"))
      (node (ref "U1") (pin "GPIO12") (pinfunction "GPIO12_GPIO12") (pintype "bidirectional"))
    )
    (net (code "61") (name "MOSI") (class "Default")
      (node (ref "IC3") (pin "13") (pinfunction "SI_13") (pintype "input"))
      (node (ref "IC4") (pin "13") (pinfunction "SI_13") (pintype "input"))
      (node (ref "IC6") (pin "13") (pinfunction "SI_13") (pintype "input"))
      (node (ref "IC9") (pin "13") (pinfunction "SI_13") (pintype "input"))
      (node (ref "U1") (pin "GPIO13") (pinfunction "GPIO13_GPIO13") (pintype "bidirectional"))
    )
    (net (code "62") (name "Net-(D1-PadA)") (class "Default")
      (node (ref "D1") (pin "A") (pinfunction "A_A") (pintype "passive"))
      (node (ref "JP1") (pin "1") (pinfunction "1_1") (pintype "passive"))
    )
    (net (code "63") (name "Net-(IC3-GPA0)") (class "Default")
      (node (ref "IC3") (pin "21") (pinfunction "GPA0_21") (pintype "bidirectional"))
      (node (ref "U$1") (pin "8") (pinfunction "IN8_8") (pintype "input"))
    )
    (net (code "64") (name "Net-(IC3-GPA1)") (class "Default")
      (node (ref "IC3") (pin "22") (pinfunction "GPA1_22") (pintype "bidirectional"))
      (node (ref "U$1") (pin "7") (pinfunction "IN7_7") (pintype "input"))
    )
    (net (code "65") (name "Net-(IC3-GPA2)") (class "Default")
      (node (ref "IC3") (pin "23") (pinfunction "GPA2_23") (pintype "bidirectional"))
      (node (ref "U$1") (pin "6") (pinfunction "IN6_6") (pintype "input"))
    )
    (net (code "66") (name "Net-(IC3-GPA3)") (class "Default")
      (node (ref "IC3") (pin "24") (pinfunction "GPA3_24") (pintype "bidirectional"))
      (node (ref "U$1") (pin "5") (pinfunction "IN5_5") (pintype "input"))
    )
    (net (code "67") (name "Net-(IC3-GPA4)") (class "Default")
      (node (ref "IC3") (pin "25") (pinfunction "GPA4_25") (pintype "bidirectional"))
      (node (ref "U$1") (pin "4") (pinfunction "IN4_4") (pintype "input"))
    )
    (net (code "68") (name "Net-(IC3-GPA5)") (class "Default")
      (node (ref "IC3") (pin "26") (pinfunction "GPA5_26") (pintype "bidirectional"))
      (node (ref "U$1") (pin "1") (pinfunction "IN1_1") (pintype "input"))
    )
    (net (code "69") (name "Net-(IC3-GPA6)") (class "Default")
      (node (ref "IC3") (pin "27") (pinfunction "GPA6_27") (pintype "bidirectional"))
      (node (ref "U$1") (pin "2") (pinfunction "IN2_2") (pintype "input"))
    )
    (net (code "70") (name "Net-(IC3-GPA7)") (class "Default")
      (node (ref "IC3") (pin "28") (pinfunction "GPA7_28") (pintype "bidirectional"))
      (node (ref "U$1") (pin "3") (pinfunction "IN3_3") (pintype "input"))
    )
    (net (code "71") (name "Net-(IC3-GPB0)") (class "Default")
      (node (ref "IC3") (pin "1") (pinfunction "GPB0_1") (pintype "bidirectional"))
      (node (ref "U$2") (pin "6") (pinfunction "IN6_6") (pintype "input"))
    )
    (net (code "72") (name "Net-(IC3-GPB1)") (class "Default")
      (node (ref "IC3") (pin "2") (pinfunction "GPB1_2") (pintype "bidirectional"))
      (node (ref "U$2") (pin "7") (pinfunction "IN7_7") (pintype "input"))
    )
    (net (code "73") (name "Net-(IC3-GPB2)") (class "Default")
      (node (ref "IC3") (pin "3") (pinfunction "GPB2_3") (pintype "bidirectional"))
      (node (ref "U$2") (pin "8") (pinfunction "IN8_8") (pintype "input"))
    )
    (net (code "74") (name "Net-(IC3-GPB3)") (class "Default")
      (node (ref "IC3") (pin "4") (pinfunction "GPB3_4") (pintype "bidirectional"))
      (node (ref "U$2") (pin "5") (pinfunction "IN5_5") (pintype "input"))
    )
    (net (code "75") (name "Net-(IC3-GPB4)") (class "Default")
      (node (ref "IC3") (pin "5") (pinfunction "GPB4_5") (pintype "bidirectional"))
      (node (ref "U$2") (pin "4") (pinfunction "IN4_4") (pintype "input"))
    )
    (net (code "76") (name "Net-(IC3-GPB5)") (class "Default")
      (node (ref "IC3") (pin "6") (pinfunction "GPB5_6") (pintype "bidirectional"))
      (node (ref "U$2") (pin "3") (pinfunction "IN3_3") (pintype "input"))
    )
    (net (code "77") (name "Net-(IC3-GPB6)") (class "Default")
      (node (ref "IC3") (pin "7") (pinfunction "GPB6_7") (pintype "bidirectional"))
      (node (ref "U$2") (pin "2") (pinfunction "IN2_2") (pintype "input"))
    )
    (net (code "78") (name "Net-(IC3-GPB7)") (class "Default")
      (node (ref "IC3") (pin "8") (pinfunction "GPB7_8") (pintype "bidirectional"))
      (node (ref "U$2") (pin "1") (pinfunction "IN1_1") (pintype "input"))
    )
    (net (code "79") (name "Net-(IC4-GPA0)") (class "Default")
      (node (ref "IC4") (pin "21") (pinfunction "GPA0_21") (pintype "bidirectional"))
      (node (ref "JP6") (pin "2") (pinfunction "2_2") (pintype "passive"))
    )
    (net (code "80") (name "Net-(IC4-GPA1)") (class "Default")
      (node (ref "IC4") (pin "22") (pinfunction "GPA1_22") (pintype "bidirectional"))
      (node (ref "JP6") (pin "3") (pinfunction "3_3") (pintype "passive"))
    )
    (net (code "81") (name "Net-(IC4-GPA2)") (class "Default")
      (node (ref "IC4") (pin "23") (pinfunction "GPA2_23") (pintype "bidirectional"))
      (node (ref "JP6") (pin "4") (pinfunction "4_4") (pintype "passive"))
    )
    (net (code "82") (name "Net-(IC4-GPA3)") (class "Default")
      (node (ref "IC4") (pin "24") (pinfunction "GPA3_24") (pintype "bidirectional"))
      (node (ref "JP6") (pin "5") (pinfunction "5_5") (pintype "passive"))
    )
    (net (code "83") (name "Net-(IC4-GPA4)") (class "Default")
      (node (ref "IC4") (pin "25") (pinfunction "GPA4_25") (pintype "bidirectional"))
      (node (ref "JP6") (pin "6") (pinfunction "6_6") (pintype "passive"))
    )
    (net (code "84") (name "Net-(IC4-GPA5)") (class "Default")
      (node (ref "IC4") (pin "26") (pinfunction "GPA5_26") (pintype "bidirectional"))
      (node (ref "JP6") (pin "7") (pinfunction "7_7") (pintype "passive"))
    )
    (net (code "85") (name "Net-(IC4-GPA6)") (class "Default")
      (node (ref "IC4") (pin "27") (pinfunction "GPA6_27") (pintype "bidirectional"))
      (node (ref "U$5") (pin "5") (pinfunction "IN5_5") (pintype "input"))
    )
    (net (code "86") (name "Net-(IC4-GPA7)") (class "Default")
      (node (ref "IC4") (pin "28") (pinfunction "GPA7_28") (pintype "bidirectional"))
      (node (ref "U$5") (pin "6") (pinfunction "IN6_6") (pintype "input"))
    )
    (net (code "87") (name "Net-(IC4-GPB0)") (class "Default")
      (node (ref "IC4") (pin "1") (pinfunction "GPB0_1") (pintype "bidirectional"))
      (node (ref "U$5") (pin "3") (pinfunction "IN3_3") (pintype "input"))
    )
    (net (code "88") (name "Net-(IC4-GPB1)") (class "Default")
      (node (ref "IC4") (pin "2") (pinfunction "GPB1_2") (pintype "bidirectional"))
      (node (ref "U$5") (pin "4") (pinfunction "IN4_4") (pintype "input"))
    )
    (net (code "89") (name "Net-(IC4-GPB2)") (class "Default")
      (node (ref "IC4") (pin "3") (pinfunction "GPB2_3") (pintype "bidirectional"))
      (node (ref "U$5") (pin "2") (pinfunction "IN2_2") (pintype "input"))
    )
    (net (code "90") (name "Net-(IC4-GPB3)") (class "Default")
      (node (ref "IC4") (pin "4") (pinfunction "GPB3_4") (pintype "bidirectional"))
      (node (ref "U$5") (pin "1") (pinfunction "IN1_1") (pintype "input"))
    )
    (net (code "91") (name "Net-(IC4-GPB4)") (class "Default")
      (node (ref "IC4") (pin "5") (pinfunction "GPB4_5") (pintype "bidirectional"))
      (node (ref "U$4") (pin "5") (pinfunction "IN5_5") (pintype "input"))
    )
    (net (code "92") (name "Net-(IC4-GPB5)") (class "Default")
      (node (ref "IC4") (pin "6") (pinfunction "GPB5_6") (pintype "bidirectional"))
      (node (ref "U$4") (pin "6") (pinfunction "IN6_6") (pintype "input"))
    )
    (net (code "93") (name "Net-(IC4-GPB6)") (class "Default")
      (node (ref "IC4") (pin "7") (pinfunction "GPB6_7") (pintype "bidirectional"))
      (node (ref "U$4") (pin "7") (pinfunction "IN7_7") (pintype "input"))
    )
    (net (code "94") (name "Net-(IC4-GPB7)") (class "Default")
      (node (ref "IC4") (pin "8") (pinfunction "GPB7_8") (pintype "bidirectional"))
      (node (ref "U$4") (pin "8") (pinfunction "IN8_8") (pintype "input"))
    )
    (net (code "95") (name "Net-(IC5-FLAGB)") (class "Default")
      (node (ref "IC5") (pin "7") (pinfunction "FLAGB_7") (pintype "output"))
      (node (ref "R7") (pin "2") (pinfunction "2_2") (pintype "passive"))
    )
    (net (code "96") (name "Net-(IC5-ISET)") (class "Default")
      (node (ref "IC5") (pin "3") (pinfunction "ISET_3") (pintype "input"))
      (node (ref "R6") (pin "2") (pinfunction "2_2") (pintype "passive"))
    )
    (net (code "97") (name "Net-(IC5-ON)") (class "Default")
      (node (ref "IC5") (pin "4") (pinfunction "ON_4") (pintype "input"))
      (node (ref "JP5") (pin "1") (pinfunction "1_1") (pintype "passive"))
    )
    (net (code "98") (name "Net-(IC5-VOUT)") (class "Default")
      (node (ref "C15") (pin "1") (pinfunction "1_1") (pintype "passive"))
      (node (ref "IC5") (pin "8") (pinfunction "VOUT_8") (pintype "power_in"))
      (node (ref "JP4") (pin "1") (pinfunction "1_1") (pintype "passive"))
    )
    (net (code "99") (name "Net-(IC6-GPA0)") (class "Default")
      (node (ref "IC6") (pin "21") (pinfunction "GPA0_21") (pintype "bidirectional"))
      (node (ref "IC7") (pin "8") (pinfunction "I8_8") (pintype "input"))
    )
    (net (code "100") (name "Net-(IC6-GPA1)") (class "Default")
      (node (ref "IC6") (pin "22") (pinfunction "GPA1_22") (pintype "bidirectional"))
      (node (ref "IC7") (pin "7") (pinfunction "I7_7") (pintype "input"))
    )
    (net (code "101") (name "Net-(IC6-GPA2)") (class "Default")
      (node (ref "IC6") (pin "23") (pinfunction "GPA2_23") (pintype "bidirectional"))
      (node (ref "IC7") (pin "6") (pinfunction "I6_6") (pintype "input"))
    )
    (net (code "102") (name "Net-(IC6-GPA3)") (class "Default")
      (node (ref "IC6") (pin "24") (pinfunction "GPA3_24") (pintype "bidirectional"))
      (node (ref "IC7") (pin "5") (pinfunction "I5_5") (pintype "input"))
    )
    (net (code "103") (name "Net-(IC6-GPA4)") (class "Default")
      (node (ref "IC6") (pin "25") (pinfunction "GPA4_25") (pintype "bidirectional"))
      (node (ref "IC7") (pin "4") (pinfunction "I4_4") (pintype "input"))
    )
    (net (code "104") (name "Net-(IC6-GPA5)") (class "Default")
      (node (ref "IC6") (pin "26") (pinfunction "GPA5_26") (pintype "bidirectional"))
      (node (ref "IC7") (pin "1") (pinfunction "I1_1") (pintype "input"))
    )
    (net (code "105") (name "Net-(IC6-GPA6)") (class "Default")
      (node (ref "IC6") (pin "27") (pinfunction "GPA6_27") (pintype "bidirectional"))
      (node (ref "IC7") (pin "2") (pinfunction "I2_2") (pintype "input"))
    )
    (net (code "106") (name "Net-(IC6-GPA7)") (class "Default")
      (node (ref "IC6") (pin "28") (pinfunction "GPA7_28") (pintype "bidirectional"))
      (node (ref "IC7") (pin "3") (pinfunction "I3_3") (pintype "input"))
    )
    (net (code "107") (name "Net-(IC6-GPB0)") (class "Default")
      (node (ref "IC6") (pin "1") (pinfunction "GPB0_1") (pintype "bidirectional"))
      (node (ref "IC8") (pin "6") (pinfunction "I6_6") (pintype "input"))
    )
    (net (code "108") (name "Net-(IC6-GPB1)") (class "Default")
      (node (ref "IC6") (pin "2") (pinfunction "GPB1_2") (pintype "bidirectional"))
      (node (ref "IC8") (pin "7") (pinfunction "I7_7") (pintype "input"))
    )
    (net (code "109") (name "Net-(IC6-GPB2)") (class "Default")
      (node (ref "IC6") (pin "3") (pinfunction "GPB2_3") (pintype "bidirectional"))
      (node (ref "IC8") (pin "8") (pinfunction "I8_8") (pintype "input"))
    )
    (net (code "110") (name "Net-(IC6-GPB3)") (class "Default")
      (node (ref "IC6") (pin "4") (pinfunction "GPB3_4") (pintype "bidirectional"))
      (node (ref "IC8") (pin "5") (pinfunction "I5_5") (pintype "input"))
    )
    (net (code "111") (name "Net-(IC6-GPB4)") (class "Default")
      (node (ref "IC6") (pin "5") (pinfunction "GPB4_5") (pintype "bidirectional"))
      (node (ref "IC8") (pin "4") (pinfunction "I4_4") (pintype "input"))
    )
    (net (code "112") (name "Net-(IC6-GPB5)") (class "Default")
      (node (ref "IC6") (pin "6") (pinfunction "GPB5_6") (pintype "bidirectional"))
      (node (ref "IC8") (pin "3") (pinfunction "I3_3") (pintype "input"))
    )
    (net (code "113") (name "Net-(IC6-GPB6)") (class "Default")
      (node (ref "IC6") (pin "7") (pinfunction "GPB6_7") (pintype "bidirectional"))
      (node (ref "IC8") (pin "2") (pinfunction "I2_2") (pintype "input"))
    )
    (net (code "114") (name "Net-(IC6-GPB7)") (class "Default")
      (node (ref "IC6") (pin "8") (pinfunction "GPB7_8") (pintype "bidirectional"))
      (node (ref "IC8") (pin "1") (pinfunction "I1_1") (pintype "input"))
    )
    (net (code "115") (name "Net-(IC9-GPA0)") (class "Default")
      (node (ref "IC9") (pin "21") (pinfunction "GPA0_21") (pintype "bidirectional"))
      (node (ref "U$3") (pin "1") (pinfunction "IN1_1") (pintype "input"))
    )
    (net (code "116") (name "Net-(IC9-GPA1)") (class "Default")
      (node (ref "IC9") (pin "22") (pinfunction "GPA1_22") (pintype "bidirectional"))
      (node (ref "U$3") (pin "2") (pinfunction "IN2_2") (pintype "input"))
    )
    (net (code "117") (name "Net-(IC9-GPA2)") (class "Default")
      (node (ref "IC9") (pin "23") (pinfunction "GPA2_23") (pintype "bidirectional"))
      (node (ref "U$3") (pin "3") (pinfunction "IN3_3") (pintype "input"))
    )
    (net (code "118") (name "Net-(IC9-GPA3)") (class "Default")
      (node (ref "IC9") (pin "24") (pinfunction "GPA3_24") (pintype "bidirectional"))
      (node (ref "U$3") (pin "4") (pinfunction "IN4_4") (pintype "input"))
    )
    (net (code "119") (name "Net-(IC9-GPA4)") (class "Default")
      (node (ref "IC9") (pin "25") (pinfunction "GPA4_25") (pintype "bidirectional"))
      (node (ref "U$3") (pin "5") (pinfunction "IN5_5") (pintype "input"))
    )
    (net (code "120") (name "Net-(IC9-GPA5)") (class "Default")
      (node (ref "IC9") (pin "26") (pinfunction "GPA5_26") (pintype "bidirectional"))
      (node (ref "U$3") (pin "6") (pinfunction "IN6_6") (pintype "input"))
    )
    (net (code "121") (name "Net-(IC9-GPA6)") (class "Default")
      (node (ref "IC9") (pin "27") (pinfunction "GPA6_27") (pintype "bidirectional"))
      (node (ref "U$3") (pin "8") (pinfunction "IN8_8") (pintype "input"))
    )
    (net (code "122") (name "Net-(IC9-GPA7)") (class "Default")
      (node (ref "IC9") (pin "28") (pinfunction "GPA7_28") (pintype "bidirectional"))
      (node (ref "U$3") (pin "7") (pinfunction "IN7_7") (pintype "input"))
    )
    (net (code "123") (name "Net-(IC11-I1)") (class "Default")
      (node (ref "IC11") (pin "1") (pinfunction "I1_1") (pintype "input"))
      (node (ref "IC9") (pin "1") (pinfunction "GPB0_1") (pintype "bidirectional"))
    )
    (net (code "124") (name "Net-(IC11-I2)") (class "Default")
      (node (ref "IC11") (pin "2") (pinfunction "I2_2") (pintype "input"))
      (node (ref "IC9") (pin "2") (pinfunction "GPB1_2") (pintype "bidirectional"))
    )
    (net (code "125") (name "Net-(IC11-I3)") (class "Default")
      (node (ref "IC11") (pin "3") (pinfunction "I3_3") (pintype "input"))
      (node (ref "IC9") (pin "3") (pinfunction "GPB2_3") (pintype "bidirectional"))
    )
    (net (code "126") (name "Net-(IC11-I4)") (class "Default")
      (node (ref "IC11") (pin "4") (pinfunction "I4_4") (pintype "input"))
      (node (ref "IC9") (pin "4") (pinfunction "GPB3_4") (pintype "bidirectional"))
    )
    (net (code "127") (name "Net-(LED1-C)") (class "Default")
      (node (ref "LED1") (pin "K") (pinfunction "C_K") (pintype "passive"))
      (node (ref "LED2") (pin "K") (pinfunction "C_K") (pintype "passive"))
      (node (ref "LED3") (pin "K") (pinfunction "C_K") (pintype "passive"))
      (node (ref "LED4") (pin "K") (pinfunction "C_K") (pintype "passive"))
      (node (ref "S3") (pin "3") (pinfunction "P_3") (pintype "passive"))
      (node (ref "S3") (pin "4") (pinfunction "P1_4") (pintype "passive"))
    )
    (net (code "128") (name "Net-(LED1-PadA)") (class "Default")
      (node (ref "LED1") (pin "A") (pinfunction "A_A") (pintype "passive"))
      (node (ref "R11") (pin "1") (pinfunction "1_1") (pintype "passive"))
    )
    (net (code "129") (name "Net-(LED2-PadA)") (class "Default")
      (node (ref "LED2") (pin "A") (pinfunction "A_A") (pintype "passive"))
      (node (ref "R10") (pin "1") (pinfunction "1_1") (pintype "passive"))
    )
    (net (code "130") (name "Net-(LED3-PadA)") (class "Default")
      (node (ref "LED3") (pin "A") (pinfunction "A_A") (pintype "passive"))
      (node (ref "R9") (pin "1") (pinfunction "1_1") (pintype "passive"))
    )
    (net (code "131") (name "Net-(LED4-PadA)") (class "Default")
      (node (ref "LED4") (pin "A") (pinfunction "A_A") (pintype "passive"))
      (node (ref "R8") (pin "1") (pinfunction "1_1") (pintype "passive"))
    )
    (net (code "132") (name "Net-(LED5-C)") (class "Default")
      (node (ref "LED5") (pin "K") (pinfunction "C_K") (pintype "passive"))
      (node (ref "R12") (pin "1") (pinfunction "1_1") (pintype "passive"))
    )
    (net (code "133") (name "Net-(LED5-PadA)") (class "Default")
      (node (ref "LED5") (pin "A") (pinfunction "A_A") (pintype "passive"))
      (node (ref "U1") (pin "GPIO5") (pinfunction "GPIO5_GPIO5") (pintype "bidirectional"))
    )
    (net (code "134") (name "Net-(R1-Pad2)") (class "Default")
      (node (ref "R1") (pin "2") (pinfunction "2_2") (pintype "passive"))
      (node (ref "U1") (pin "GPIO15") (pinfunction "GPIO15_GPIO15") (pintype "bidirectional"))
    )
    (net (code "135") (name "Net-(R2-Pad2)") (class "Default")
      (node (ref "R2") (pin "2") (pinfunction "2_2") (pintype "passive"))
      (node (ref "U1") (pin "GPIO2") (pinfunction "GPIO2_GPIO2") (pintype "bidirectional"))
    )
    (net (code "136") (name "Net-(R3-Pad1)") (class "Default")
      (node (ref "R3") (pin "1") (pinfunction "1_1") (pintype "passive"))
      (node (ref "U1") (pin "CH_PD") (pinfunction "CH_PD_CH_PD") (pintype "bidirectional"))
    )
    (net (code "137") (name "PROG") (class "Default")
      (node (ref "R4") (pin "1") (pinfunction "1_1") (pintype "passive"))
      (node (ref "S1") (pin "3") (pinfunction "P_3") (pintype "passive"))
      (node (ref "S1") (pin "4") (pinfunction "P1_4") (pintype "passive"))
      (node (ref "U1") (pin "GPIO0") (pinfunction "GPIO0_GPIO0") (pintype "bidirectional"))
    )
    (net (code "138") (name "RESET") (class "Default")
      (node (ref "IC3") (pin "18") (pinfunction "~{RESET}_18") (pintype "input"))
      (node (ref "IC4") (pin "18") (pinfunction "~{RESET}_18") (pintype "input"))
      (node (ref "IC6") (pin "18") (pinfunction "~{RESET}_18") (pintype "input"))
      (node (ref "IC9") (pin "18") (pinfunction "~{RESET}_18") (pintype "input"))
      (node (ref "R5") (pin "2") (pinfunction "2_2") (pintype "passive"))
      (node (ref "S2") (pin "3") (pinfunction "P_3") (pintype "passive"))
      (node (ref "S2") (pin "4") (pinfunction "P1_4") (pintype "passive"))
      (node (ref "U1") (pin "RESET") (pinfunction "RESET_RESET") (pintype "bidirectional"))
    )
    (net (code "139") (name "RX") (class "Default")
      (node (ref "JP3") (pin "2") (pinfunction "2_2") (pintype "passive"))
      (node (ref "U1") (pin "RXD0") (pinfunction "RX_RXD0") (pintype "bidirectional"))
    )
    (net (code "140") (name "SCK") (class "Default")
      (node (ref "IC3") (pin "12") (pinfunction "SCK_12") (pintype "input"))
      (node (ref "IC4") (pin "12") (pinfunction "SCK_12") (pintype "input"))
      (node (ref "IC6") (pin "12") (pinfunction "SCK_12") (pintype "input"))
      (node (ref "IC9") (pin "12") (pinfunction "SCK_12") (pintype "input"))
      (node (ref "U1") (pin "GPIO14") (pinfunction "GPIO14_GPIO14") (pintype "bidirectional"))
    )
    (net (code "141") (name "TX") (class "Default")
      (node (ref "JP3") (pin "3") (pinfunction "3_3") (pintype "passive"))
      (node (ref "U1") (pin "TXD0") (pinfunction "TX_TXD0") (pintype "bidirectional"))
    )
    (net (code "142") (name "VS") (class "Default")
      (node (ref "IC11") (pin "9") (pinfunction "VS_9") (pintype "passive"))
      (node (ref "IC7") (pin "9") (pinfunction "VS_9") (pintype "passive"))
      (node (ref "IC8") (pin "9") (pinfunction "VS_9") (pintype "passive"))
      (node (ref "JP4") (pin "2") (pinfunction "2_2") (pintype "passive"))
      (node (ref "R9") (pin "2") (pinfunction "2_2") (pintype "passive"))
      (node (ref "X1") (pin "44") (pinfunction "S_44") (pintype "passive"))
    )
    (net (code "143") (name "unconnected-(IC3-INTA-Pad20)") (class "Default")
      (node (ref "IC3") (pin "20") (pinfunction "INTA_20") (pintype "output"))
    )
    (net (code "144") (name "unconnected-(IC3-INTB-Pad19)") (class "Default")
      (node (ref "IC3") (pin "19") (pinfunction "INTB_19") (pintype "output"))
    )
    (net (code "145") (name "unconnected-(IC4-INTA-Pad20)") (class "Default")
      (node (ref "IC4") (pin "20") (pinfunction "INTA_20") (pintype "output"))
    )
    (net (code "146") (name "unconnected-(IC4-INTB-Pad19)") (class "Default")
      (node (ref "IC4") (pin "19") (pinfunction "INTB_19") (pintype "output"))
    )
    (net (code "147") (name "unconnected-(IC6-INTA-Pad20)") (class "Default")
      (node (ref "IC6") (pin "20") (pinfunction "INTA_20") (pintype "output"))
    )
    (net (code "148") (name "unconnected-(IC6-INTB-Pad19)") (class "Default")
      (node (ref "IC6") (pin "19") (pinfunction "INTB_19") (pintype "output"))
    )
    (net (code "149") (name "unconnected-(IC9-GPB4-Pad5)") (class "Default")
      (node (ref "IC9") (pin "5") (pinfunction "GPB4_5") (pintype "bidirectional"))
    )
    (net (code "150") (name "unconnected-(IC9-GPB5-Pad6)") (class "Default")
      (node (ref "IC9") (pin "6") (pinfunction "GPB5_6") (pintype "bidirectional"))
    )
    (net (code "151") (name "unconnected-(IC9-GPB6-Pad7)") (class "Default")
      (node (ref "IC9") (pin "7") (pinfunction "GPB6_7") (pintype "bidirectional"))
    )
    (net (code "152") (name "unconnected-(IC9-GPB7-Pad8)") (class "Default")
      (node (ref "IC9") (pin "8") (pinfunction "GPB7_8") (pintype "bidirectional"))
    )
    (net (code "153") (name "unconnected-(IC9-INTA-Pad20)") (class "Default")
      (node (ref "IC9") (pin "20") (pinfunction "INTA_20") (pintype "output"))
    )
    (net (code "154") (name "unconnected-(IC9-INTB-Pad19)") (class "Default")
      (node (ref "IC9") (pin "19") (pinfunction "INTB_19") (pintype "output"))
    )
    (net (code "155") (name "unconnected-(IC11-I5-Pad5)") (class "Default")
      (node (ref "IC11") (pin "5") (pinfunction "I5_5") (pintype "input"))
    )
    (net (code "156") (name "unconnected-(IC11-I6-Pad6)") (class "Default")
      (node (ref "IC11") (pin "6") (pinfunction "I6_6") (pintype "input"))
    )
    (net (code "157") (name "unconnected-(IC11-I7-Pad7)") (class "Default")
      (node (ref "IC11") (pin "7") (pinfunction "I7_7") (pintype "input"))
    )
    (net (code "158") (name "unconnected-(IC11-I8-Pad8)") (class "Default")
      (node (ref "IC11") (pin "8") (pinfunction "I8_8") (pintype "input"))
    )
    (net (code "159") (name "unconnected-(IC11-O5-Pad14)") (class "Default")
      (node (ref "IC11") (pin "14") (pinfunction "O5_14") (pintype "open_collector"))
    )
    (net (code "160") (name "unconnected-(IC11-O6-Pad13)") (class "Default")
      (node (ref "IC11") (pin "13") (pinfunction "O6_13") (pintype "open_collector"))
    )
    (net (code "161") (name "unconnected-(IC11-O7-Pad12)") (class "Default")
      (node (ref "IC11") (pin "12") (pinfunction "O7_12") (pintype "open_collector"))
    )
    (net (code "162") (name "unconnected-(IC11-O8-Pad11)") (class "Default")
      (node (ref "IC11") (pin "11") (pinfunction "O8_11") (pintype "open_collector"))
    )
    (net (code "163") (name "unconnected-(U$4-IN1-Pad1)") (class "Default")
      (node (ref "U$4") (pin "1") (pinfunction "IN1_1") (pintype "input"))
    )
    (net (code "164") (name "unconnected-(U$4-IN2-Pad2)") (class "Default")
      (node (ref "U$4") (pin "2") (pinfunction "IN2_2") (pintype "input"))
    )
    (net (code "165") (name "unconnected-(U$4-IN3-Pad3)") (class "Default")
      (node (ref "U$4") (pin "3") (pinfunction "IN3_3") (pintype "input"))
    )
    (net (code "166") (name "unconnected-(U$4-IN4-Pad4)") (class "Default")
      (node (ref "U$4") (pin "4") (pinfunction "IN4_4") (pintype "input"))
    )
    (net (code "167") (name "unconnected-(U$4-OUT1-Pad18)") (class "Default")
      (node (ref "U$4") (pin "18") (pinfunction "OUT1_18") (pintype "open_collector"))
    )
    (net (code "168") (name "unconnected-(U$4-OUT2-Pad17)") (class "Default")
      (node (ref "U$4") (pin "17") (pinfunction "OUT2_17") (pintype "open_collector"))
    )
    (net (code "169") (name "unconnected-(U$4-OUT3-Pad16)") (class "Default")
      (node (ref "U$4") (pin "16") (pinfunction "OUT3_16") (pintype "open_collector"))
    )
    (net (code "170") (name "unconnected-(U$4-OUT4-Pad15)") (class "Default")
      (node (ref "U$4") (pin "15") (pinfunction "OUT4_15") (pintype "open_collector"))
    )
    (net (code "171") (name "unconnected-(U$5-IN7-Pad7)") (class "Default")
      (node (ref "U$5") (pin "7") (pinfunction "IN7_7") (pintype "input"))
    )
    (net (code "172") (name "unconnected-(U$5-IN8-Pad8)") (class "Default")
      (node (ref "U$5") (pin "8") (pinfunction "IN8_8") (pintype "input"))
    )
    (net (code "173") (name "unconnected-(U$5-OUT7-Pad12)") (class "Default")
      (node (ref "U$5") (pin "12") (pinfunction "OUT7_12") (pintype "open_collector"))
    )
    (net (code "174") (name "unconnected-(U$5-OUT8-Pad11)") (class "Default")
      (node (ref "U$5") (pin "11") (pinfunction "OUT8_11") (pintype "open_collector"))
    )
    (net (code "175") (name "unconnected-(U1-PadADC)") (class "Default")
      (node (ref "U1") (pin "ADC") (pinfunction "ADC_ADC") (pintype "bidirectional"))
    )
    (net (code "176") (name "unconnected-(U1-PadGPIO16)") (class "Default")
      (node (ref "U1") (pin "GPIO16") (pinfunction "GPIO16_GPIO16") (pintype "bidirectional"))
    )
    (net (code "177") (name "unconnected-(X1AO-S-Pad46)") (class "Default")
      (node (ref "X1") (pin "46") (pinfunction "S_46") (pintype "passive"))
    )
  )
)
